# DISPLAY_BOARD.net
KiCad netlist of a schematic drawn in Altium Designer
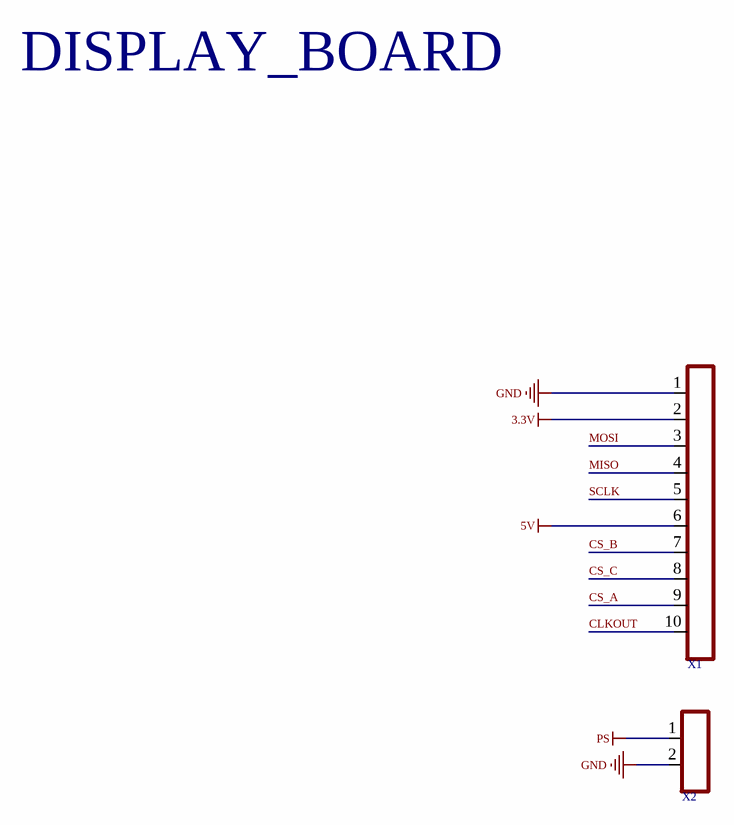
[diagram p0: DISPLAY_BOARD.SchDoc]

(export (version "E")
  (design (tool "Eeschema 10.0.6"))
  (components
    (comp (ref "X1") (value "BH-10") (footprint "PBD-10") (libsource (lib "BH-10") (part "BH-10")))
    (comp (ref "X2")
      (value "CONN-2-PIN")
      (footprint "CONN-PLS-2")
      (libsource (lib "PLS-5__") (part "CONN-2-PIN"))
    )
  )
  (nets
    (net (code "1") (name "/CLKOUT") (class "Default")
      (node (ref "X1") (pin "10") (pinfunction "10_10") (pintype "passive"))
    )
    (net (code "2") (name "/CS_A") (class "Default")
      (node (ref "X1") (pin "9") (pinfunction "9_9") (pintype "passive"))
    )
    (net (code "3") (name "/CS_B") (class "Default")
      (node (ref "X1") (pin "7") (pinfunction "7_7") (pintype "passive"))
    )
    (net (code "4") (name "/CS_C") (class "Default")
      (node (ref "X1") (pin "8") (pinfunction "8_8") (pintype "passive"))
    )
    (net (code "5") (name "/MISO") (class "Default")
      (node (ref "X1") (pin "4") (pinfunction "4_4") (pintype "passive"))
    )
    (net (code "6") (name "/MOSI") (class "Default")
      (node (ref "X1") (pin "3") (pinfunction "3_3") (pintype "passive"))
    )
    (net (code "7") (name "/SCLK") (class "Default")
      (node (ref "X1") (pin "5") (pinfunction "5_5") (pintype "passive"))
    )
    (net (code "8") (name "3.3V") (class "Default")
      (node (ref "X1") (pin "2") (pinfunction "2_2") (pintype "passive"))
    )
    (net (code "9") (name "5V") (class "Default")
      (node (ref "X1") (pin "6") (pinfunction "6_6") (pintype "passive"))
    )
    (net (code "10") (name "GND") (class "Default")
      (node (ref "X1") (pin "1") (pinfunction "1_1") (pintype "passive"))
      (node (ref "X2") (pin "2") (pinfunction "2_2") (pintype "passive"))
    )
    (net (code "11") (name "PS") (class "Default")
      (node (ref "X2") (pin "1") (pinfunction "1_1") (pintype "passive"))
    )
  )
)
